# xplorer_t.net
KiCad netlist of a schematic drawn in EAGLE
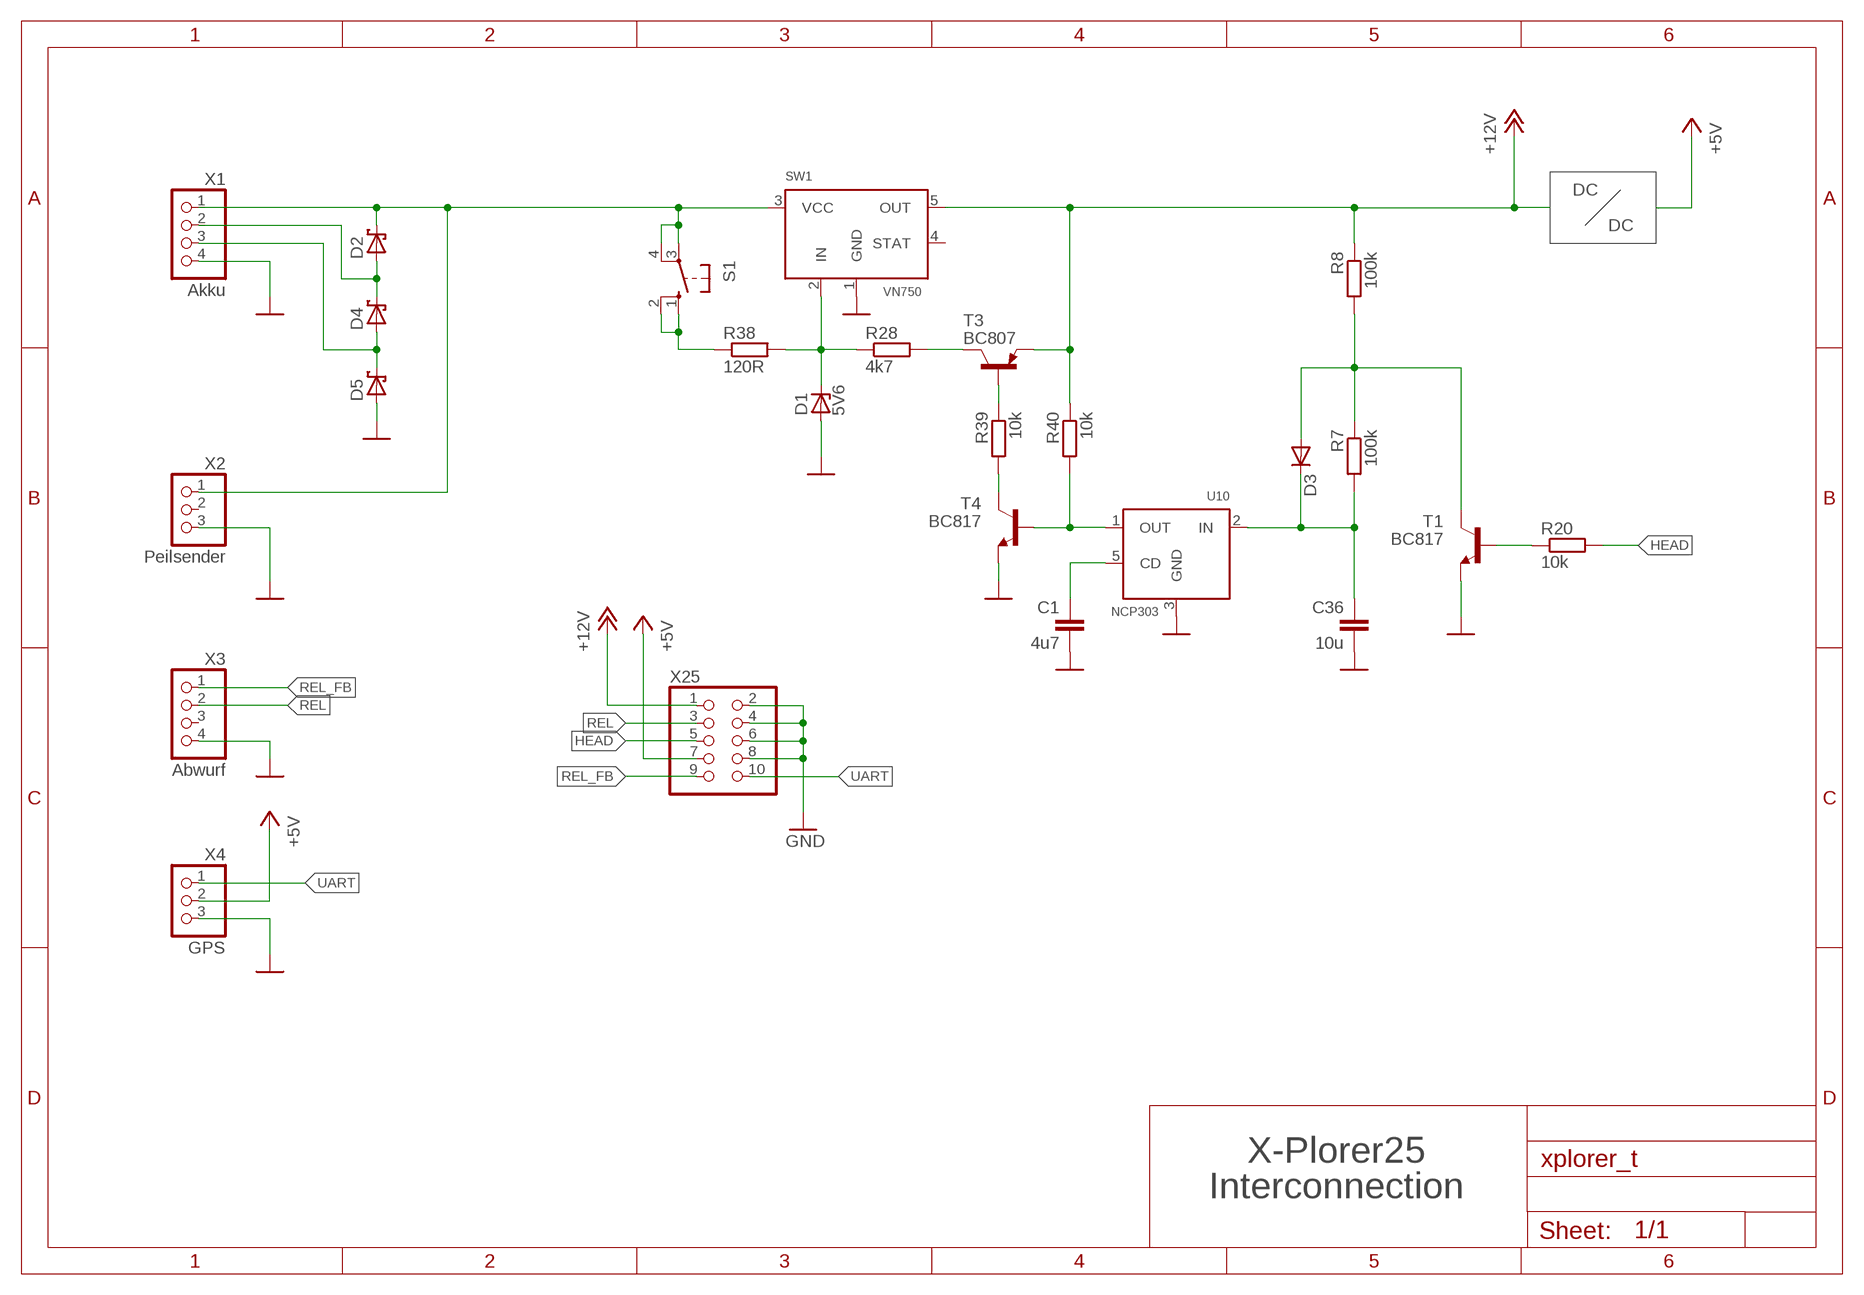
[diagram p0: schematic, sheet 1]

(export (version "E")
  (design (tool "Eeschema 10.0.6"))
  (components
    (comp (ref "C1")
      (value "4u7")
      (footprint "eagle-import:C1210")
      (libsource (lib "eagle-import") (part "C-EUC1210"))
    )
    (comp (ref "C36")
      (value "10u")
      (footprint "eagle-import:C1210")
      (libsource (lib "eagle-import") (part "C-EUC1210"))
    )
    (comp (ref "D1")
      (value "5V6")
      (footprint "eagle-import:SOT23")
      (libsource (lib "eagle-import") (part "ZENER-DIODESOT23"))
    )
    (comp (ref "D2")
      (value "MBRS130LT3")
      (footprint "eagle-import:SMB")
      (libsource (lib "eagle-import") (part "MBRS130LT3"))
    )
    (comp (ref "D3")
      (value "DIODE-MINIMELF")
      (footprint "eagle-import:MINIMELF")
      (libsource (lib "eagle-import") (part "DIODE-MINIMELF"))
    )
    (comp (ref "D4")
      (value "MBRS130LT3")
      (footprint "eagle-import:SMB")
      (libsource (lib "eagle-import") (part "MBRS130LT3"))
    )
    (comp (ref "D5")
      (value "MBRS130LT3")
      (footprint "eagle-import:SMB")
      (libsource (lib "eagle-import") (part "MBRS130LT3"))
    )
    (comp (ref "R7")
      (value "100k")
      (footprint "eagle-import:R0805")
      (libsource (lib "eagle-import") (part "R-EU_R0805"))
    )
    (comp (ref "R8")
      (value "100k")
      (footprint "eagle-import:R0805")
      (libsource (lib "eagle-import") (part "R-EU_R0805"))
    )
    (comp (ref "R20")
      (value "10k")
      (footprint "eagle-import:R0805")
      (libsource (lib "eagle-import") (part "R-EU_R0805"))
    )
    (comp (ref "R28")
      (value "4k7")
      (footprint "eagle-import:R0805")
      (libsource (lib "eagle-import") (part "R-EU_R0805"))
    )
    (comp (ref "R38")
      (value "120R")
      (footprint "eagle-import:R1206")
      (libsource (lib "eagle-import") (part "R-EU_R1206"))
    )
    (comp (ref "R39")
      (value "10k")
      (footprint "eagle-import:R0805")
      (libsource (lib "eagle-import") (part "R-EU_R0805"))
    )
    (comp (ref "R40")
      (value "10k")
      (footprint "eagle-import:R0805")
      (libsource (lib "eagle-import") (part "R-EU_R0805"))
    )
    (comp (ref "S1")
      (value "10-XX")
      (footprint "eagle-import:B3F-10XX")
      (fields (field (name "MPN") "B3F-1000"))
      (libsource (lib "eagle-import") (part "10-XX"))
    )
    (comp (ref "SW1")
      (value "VN750")
      (footprint "eagle-import:DDPAK")
      (libsource (lib "eagle-import") (part "VN750"))
    )
    (comp (ref "T1")
      (value "BC817")
      (footprint "eagle-import:SOT23-BEC")
      (libsource (lib "eagle-import") (part "BC817SMD-16LT1"))
    )
    (comp (ref "T3")
      (value "BC807")
      (footprint "eagle-import:SOT23-BEC")
      (libsource (lib "eagle-import") (part "BC807SMD-16LT1"))
    )
    (comp (ref "T4")
      (value "BC817")
      (footprint "eagle-import:SOT23-BEC")
      (libsource (lib "eagle-import") (part "BC817SMD-16LT1"))
    )
    (comp (ref "U10")
      (value "NCP303")
      (footprint "eagle-import:SOT23-DBV")
      (libsource (lib "eagle-import") (part "NCP303"))
    )
    (comp (ref "X1")
      (value "Akku")
      (footprint "eagle-import:1X04")
      (libsource (lib "eagle-import") (part "PINHD-1X4"))
    )
    (comp (ref "X2")
      (value "Peilsender")
      (footprint "eagle-import:1X03_90")
      (libsource (lib "eagle-import") (part "PINHD-1X3/90"))
    )
    (comp (ref "X3")
      (value "Abwurf")
      (footprint "eagle-import:1X04_90")
      (libsource (lib "eagle-import") (part "PINHD-1X4/90"))
    )
    (comp (ref "X4")
      (value "GPS")
      (footprint "eagle-import:1X03")
      (libsource (lib "eagle-import") (part "PINHD-1X3"))
    )
    (comp (ref "X25")
      (value "PINHD-2X5")
      (footprint "eagle-import:2X05")
      (libsource (lib "eagle-import") (part "PINHD-2X5"))
    )
  )
  (nets
    (net (code "1") (name "+5V") (class "Default")
      (node (ref "X25") (pin "7") (pinfunction "7_7") (pintype "passive"))
      (node (ref "X4") (pin "2") (pinfunction "2_2") (pintype "passive"))
    )
    (net (code "2") (name "+12V") (class "Default")
      (node (ref "R40") (pin "1") (pinfunction "1_1") (pintype "passive"))
      (node (ref "R8") (pin "1") (pinfunction "1_1") (pintype "passive"))
      (node (ref "SW1") (pin "5") (pinfunction "OUT_5") (pintype "power_in"))
      (node (ref "T3") (pin "E") (pinfunction "E_E") (pintype "passive"))
      (node (ref "X25") (pin "1") (pinfunction "1_1") (pintype "passive"))
    )
    (net (code "3") (name "GND") (class "Default")
      (node (ref "C1") (pin "2") (pinfunction "2_2") (pintype "passive"))
      (node (ref "C36") (pin "2") (pinfunction "2_2") (pintype "passive"))
      (node (ref "D1") (pin "1") (pinfunction "A_1") (pintype "passive"))
      (node (ref "D5") (pin "A") (pinfunction "A_A") (pintype "passive"))
      (node (ref "SW1") (pin "1") (pinfunction "GND_1") (pintype "power_in"))
      (node (ref "T1") (pin "E") (pinfunction "E_E") (pintype "passive"))
      (node (ref "T4") (pin "E") (pinfunction "E_E") (pintype "passive"))
      (node (ref "U10") (pin "3") (pinfunction "GND_3") (pintype "power_in"))
      (node (ref "X1") (pin "4") (pinfunction "4_4") (pintype "passive"))
      (node (ref "X2") (pin "3") (pinfunction "3_3") (pintype "passive"))
      (node (ref "X25") (pin "2") (pinfunction "2_2") (pintype "passive"))
      (node (ref "X25") (pin "4") (pinfunction "4_4") (pintype "passive"))
      (node (ref "X25") (pin "6") (pinfunction "6_6") (pintype "passive"))
      (node (ref "X25") (pin "8") (pinfunction "8_8") (pintype "passive"))
      (node (ref "X3") (pin "4") (pinfunction "4_4") (pintype "passive"))
      (node (ref "X4") (pin "3") (pinfunction "3_3") (pintype "passive"))
    )
    (net (code "4") (name "HEAD") (class "Default")
      (node (ref "R20") (pin "2") (pinfunction "2_2") (pintype "passive"))
      (node (ref "X25") (pin "5") (pinfunction "5_5") (pintype "passive"))
    )
    (net (code "5") (name "Net-(D1-C)") (class "Default")
      (node (ref "D1") (pin "3") (pinfunction "C_3") (pintype "passive"))
      (node (ref "R28") (pin "1") (pinfunction "1_1") (pintype "passive"))
      (node (ref "R38") (pin "2") (pinfunction "2_2") (pintype "passive"))
      (node (ref "SW1") (pin "2") (pinfunction "IN_2") (pintype "input"))
    )
    (net (code "6") (name "Net-(D2-PadA)") (class "Default")
      (node (ref "D2") (pin "A") (pinfunction "A_A") (pintype "passive"))
      (node (ref "D4") (pin "C") (pinfunction "C_C") (pintype "passive"))
      (node (ref "X1") (pin "2") (pinfunction "2_2") (pintype "passive"))
    )
    (net (code "7") (name "Net-(D3-PadA)") (class "Default")
      (node (ref "D3") (pin "A") (pinfunction "A_A") (pintype "passive"))
      (node (ref "R7") (pin "1") (pinfunction "1_1") (pintype "passive"))
      (node (ref "R8") (pin "2") (pinfunction "2_2") (pintype "passive"))
      (node (ref "T1") (pin "C") (pinfunction "C_C") (pintype "passive"))
    )
    (net (code "8") (name "Net-(D4-PadA)") (class "Default")
      (node (ref "D4") (pin "A") (pinfunction "A_A") (pintype "passive"))
      (node (ref "D5") (pin "C") (pinfunction "C_C") (pintype "passive"))
      (node (ref "X1") (pin "3") (pinfunction "3_3") (pintype "passive"))
    )
    (net (code "9") (name "Net-(R20-Pad1)") (class "Default")
      (node (ref "R20") (pin "1") (pinfunction "1_1") (pintype "passive"))
      (node (ref "T1") (pin "B") (pinfunction "B_B") (pintype "passive"))
    )
    (net (code "10") (name "Net-(R28-Pad2)") (class "Default")
      (node (ref "R28") (pin "2") (pinfunction "2_2") (pintype "passive"))
      (node (ref "T3") (pin "C") (pinfunction "C_C") (pintype "passive"))
    )
    (net (code "11") (name "Net-(R39-Pad1)") (class "Default")
      (node (ref "R39") (pin "1") (pinfunction "1_1") (pintype "passive"))
      (node (ref "T3") (pin "B") (pinfunction "B_B") (pintype "passive"))
    )
    (net (code "12") (name "Net-(R39-Pad2)") (class "Default")
      (node (ref "R39") (pin "2") (pinfunction "2_2") (pintype "passive"))
      (node (ref "T4") (pin "C") (pinfunction "C_C") (pintype "passive"))
    )
    (net (code "13") (name "Net-(S1-P)") (class "Default")
      (node (ref "D2") (pin "C") (pinfunction "C_C") (pintype "passive"))
      (node (ref "S1") (pin "3") (pinfunction "P_3") (pintype "passive"))
      (node (ref "S1") (pin "4") (pinfunction "P1_4") (pintype "passive"))
      (node (ref "SW1") (pin "3") (pinfunction "VCC_3") (pintype "power_in"))
      (node (ref "X1") (pin "1") (pinfunction "1_1") (pintype "passive"))
      (node (ref "X2") (pin "1") (pinfunction "1_1") (pintype "passive"))
    )
    (net (code "14") (name "Net-(S1-S)") (class "Default")
      (node (ref "R38") (pin "1") (pinfunction "1_1") (pintype "passive"))
      (node (ref "S1") (pin "1") (pinfunction "S_1") (pintype "passive"))
      (node (ref "S1") (pin "2") (pinfunction "S1_2") (pintype "passive"))
    )
    (net (code "15") (name "Net-(U10-CD)") (class "Default")
      (node (ref "C1") (pin "1") (pinfunction "1_1") (pintype "passive"))
      (node (ref "U10") (pin "5") (pinfunction "CD_5") (pintype "passive"))
    )
    (net (code "16") (name "Net-(U10-IN)") (class "Default")
      (node (ref "C36") (pin "1") (pinfunction "1_1") (pintype "passive"))
      (node (ref "D3") (pin "C") (pinfunction "C_C") (pintype "passive"))
      (node (ref "R7") (pin "2") (pinfunction "2_2") (pintype "passive"))
      (node (ref "U10") (pin "2") (pinfunction "IN_2") (pintype "input"))
    )
    (net (code "17") (name "Net-(U10-OUT)") (class "Default")
      (node (ref "R40") (pin "2") (pinfunction "2_2") (pintype "passive"))
      (node (ref "T4") (pin "B") (pinfunction "B_B") (pintype "passive"))
      (node (ref "U10") (pin "1") (pinfunction "OUT_1") (pintype "output"))
    )
    (net (code "18") (name "REL") (class "Default")
      (node (ref "X25") (pin "3") (pinfunction "3_3") (pintype "passive"))
      (node (ref "X3") (pin "2") (pinfunction "2_2") (pintype "passive"))
    )
    (net (code "19") (name "REL_FB") (class "Default")
      (node (ref "X25") (pin "9") (pinfunction "9_9") (pintype "passive"))
      (node (ref "X3") (pin "1") (pinfunction "1_1") (pintype "passive"))
    )
    (net (code "20") (name "UART") (class "Default")
      (node (ref "X25") (pin "10") (pinfunction "10_10") (pintype "passive"))
      (node (ref "X4") (pin "1") (pinfunction "1_1") (pintype "passive"))
    )
    (net (code "21") (name "unconnected-(SW1-STAT-Pad4)") (class "Default")
      (node (ref "SW1") (pin "4") (pinfunction "STAT_4") (pintype "output"))
    )
    (net (code "22") (name "unconnected-(X2-Pad2)") (class "Default")
      (node (ref "X2") (pin "2") (pinfunction "2_2") (pintype "passive"))
    )
    (net (code "23") (name "unconnected-(X3-Pad3)") (class "Default")
      (node (ref "X3") (pin "3") (pinfunction "3_3") (pintype "passive"))
    )
  )
)
